# fan.net
KiCad netlist of a schematic drawn in Altium Designer
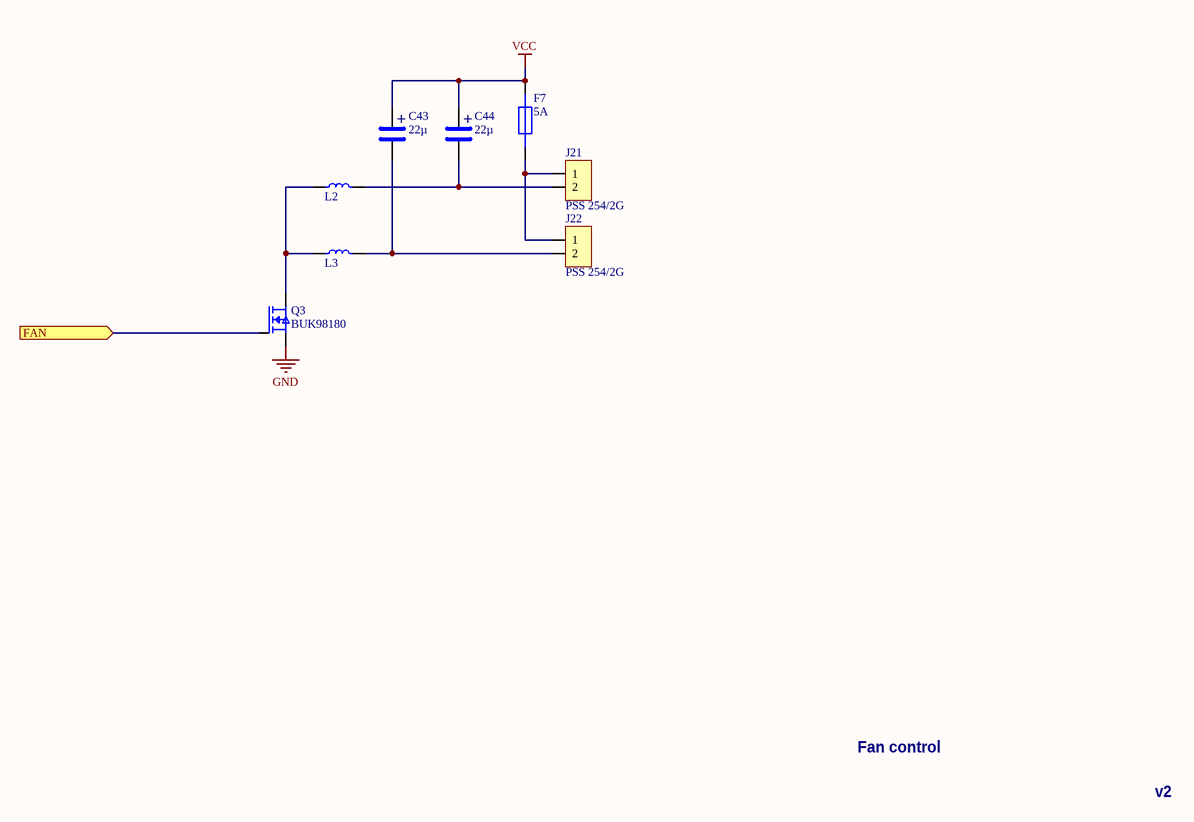
[diagram p0: fan.SchDoc]

(export (version "E")
  (design (tool "Eeschema 10.0.6"))
  (components
    (comp (ref "C43")
      (value "22µ")
      (footprint "WCAP-ASLU")
      (fields (field (name "VOLTAGE") "6.3V") (field (name "Comment") "Elko 22µF 6.3V WE"))
      (libsource (lib "elko") (part "Elko 22µF 6.3V WE"))
    )
    (comp (ref "C44")
      (value "22µ")
      (footprint "WCAP-ASLU")
      (fields (field (name "VOLTAGE") "6.3V") (field (name "Comment") "Elko 22µF 6.3V WE"))
      (libsource (lib "elko") (part "Elko 22µF 6.3V WE"))
    )
    (comp (ref "F7")
      (value "5A")
      (footprint "1206")
      (description "Fuse, 1206, 1A, 63VDC / 63VAC")
      (libsource (lib "misc") (part "Fuse_1206_1A"))
    )
    (comp (ref "J21")
      (value "PSS 254/2G")
      (footprint "PSS 2pol")
      (description "PSS 2pol wire-to-board-connector")
      (libsource (lib "connectors_pss") (part "PSS 254/2G"))
    )
    (comp (ref "J22")
      (value "PSS 254/2G")
      (footprint "PSS 2pol")
      (description "PSS 2pol wire-to-board-connector")
      (libsource (lib "connectors_pss") (part "PSS 254/2G"))
    )
    (comp (ref "L2")
      (value "TDL_NL322522")
      (footprint "NL322522")
      (libsource (lib "inductors") (part "TDL_NL322522"))
    )
    (comp (ref "L3")
      (value "TDL_NL322522")
      (footprint "NL322522")
      (libsource (lib "inductors") (part "TDL_NL322522"))
    )
    (comp (ref "Q3")
      (value "BUK98180")
      (footprint "SOT223")
      (description "N-FET 100V 4.6A logic level")
      (libsource (lib "semiconductors") (part "BUK98180-100A"))
    )
  )
  (nets
    (net (code "1") (name "/FAN") (class "Default")
      (node (ref "Q3") (pin "1") (pinfunction "1_1") (pintype "passive"))
    )
    (net (code "2") (name "GND") (class "Default")
      (node (ref "Q3") (pin "3") (pinfunction "3_3") (pintype "passive"))
    )
    (net (code "3") (name "Net-(C43-Pad-)") (class "Default")
      (node (ref "C43") (pin "-") (pinfunction "-_-") (pintype "passive"))
      (node (ref "J22") (pin "2") (pinfunction "2_2") (pintype "passive"))
      (node (ref "L3") (pin "2") (pinfunction "2_2") (pintype "passive"))
    )
    (net (code "4") (name "Net-(C44-Pad-)") (class "Default")
      (node (ref "C44") (pin "-") (pinfunction "-_-") (pintype "passive"))
      (node (ref "J21") (pin "2") (pinfunction "2_2") (pintype "passive"))
      (node (ref "L2") (pin "2") (pinfunction "2_2") (pintype "passive"))
    )
    (net (code "5") (name "Net-(F7-Pad1)") (class "Default")
      (node (ref "F7") (pin "1") (pinfunction "1_1") (pintype "passive"))
      (node (ref "J21") (pin "1") (pinfunction "1_1") (pintype "passive"))
      (node (ref "J22") (pin "1") (pinfunction "1_1") (pintype "passive"))
    )
    (net (code "6") (name "Net-(L2-Pad1)") (class "Default")
      (node (ref "L2") (pin "1") (pinfunction "1_1") (pintype "passive"))
      (node (ref "L3") (pin "1") (pinfunction "1_1") (pintype "passive"))
      (node (ref "Q3") (pin "2") (pinfunction "2_2") (pintype "passive"))
    )
    (net (code "7") (name "VCC") (class "Default")
      (node (ref "C43") (pin "+") (pinfunction "+_+") (pintype "passive"))
      (node (ref "C44") (pin "+") (pinfunction "+_+") (pintype "passive"))
      (node (ref "F7") (pin "2") (pinfunction "2_2") (pintype "passive"))
    )
  )
)
